# SCH_PCBBoardProject_2022-06-28.net
KiCad netlist of a schematic drawn in EasyEDA
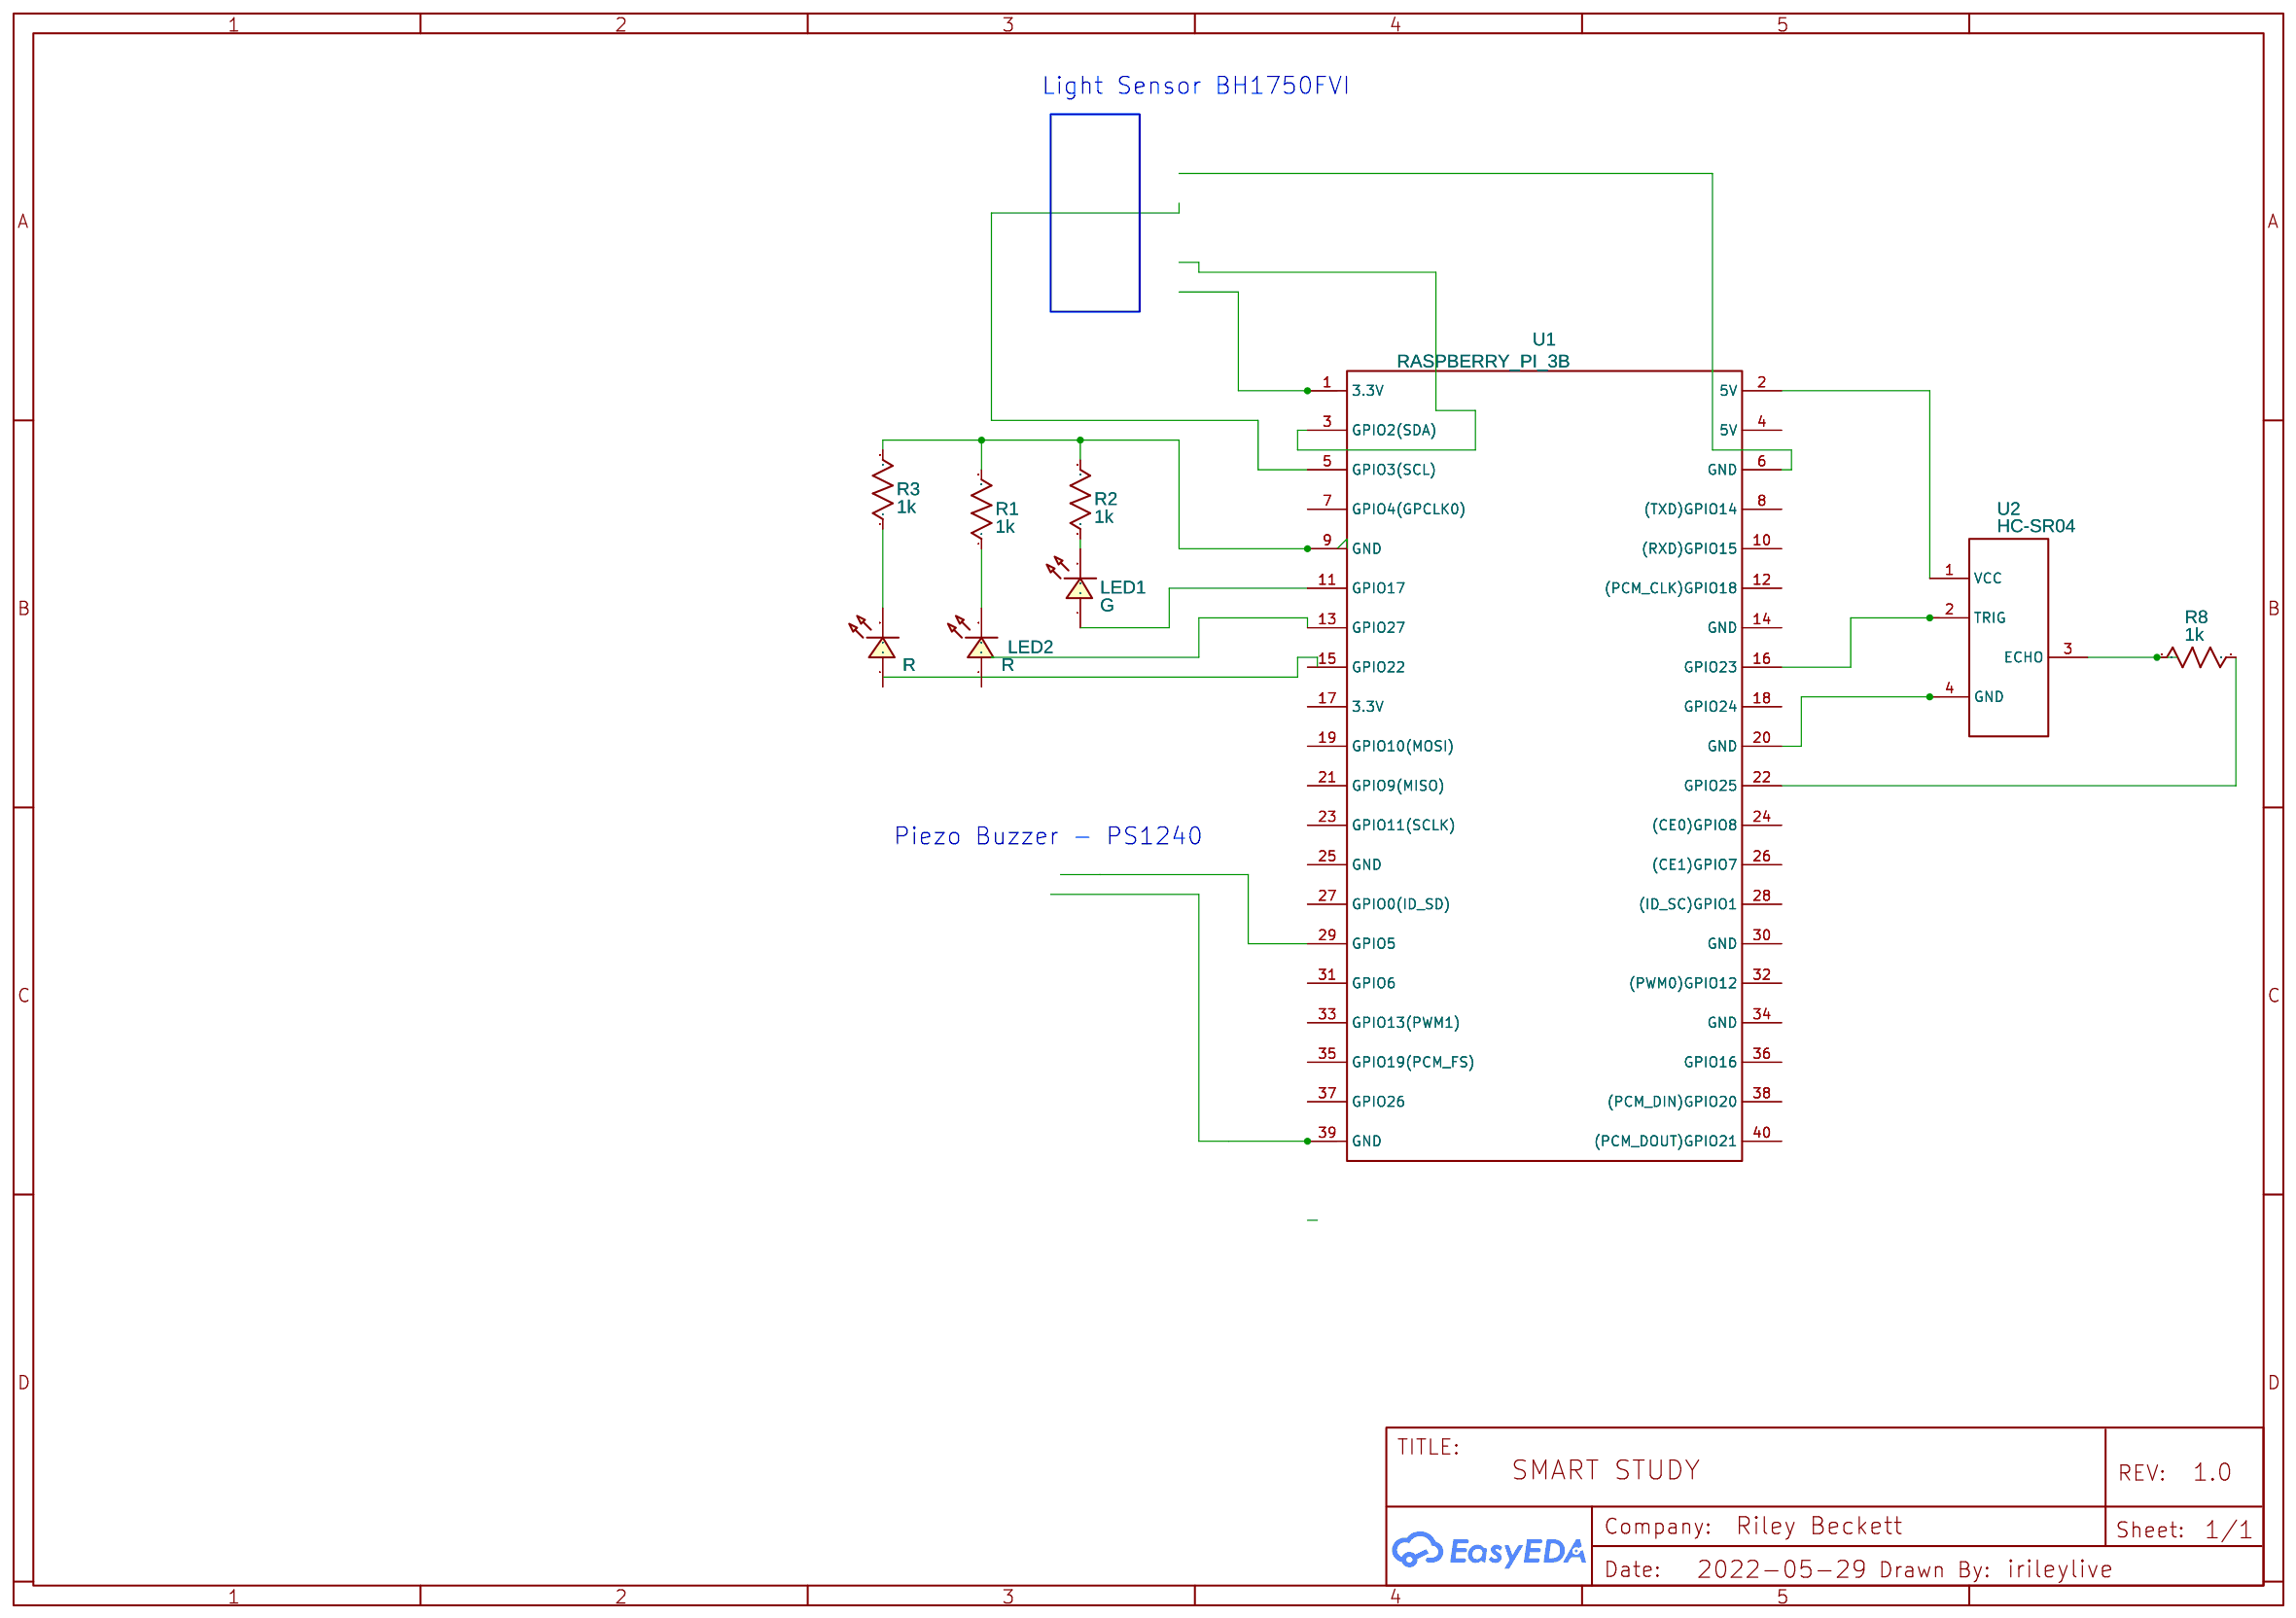
[diagram p0: schematic sheet]

(export (version "E")
  (design (tool "Eeschema 10.0.6"))
  (components
    (comp (ref "LED1")
      (value "G")
      (fields
        (field (name "BOM_Manufacturer Part") "204-10SYGD/S530-E3")
        (field (name "BOM_Supplier Part") "C85161")
      )
      (libsource (lib "") (part "LED-TH-3mm_G"))
    )
    (comp (ref "LED2")
      (value "R")
      (fields
        (field (name "BOM_Manufacturer Part") "204-10SDRD/S530-A3-L")
        (field (name "BOM_Supplier Part") "C84774")
      )
      (libsource (lib "") (part "LED-TH-3mm_R"))
    )
    (comp (ref "LED3")
      (value "R")
      (fields
        (field (name "BOM_Manufacturer Part") "204-10SDRD/S530-A3-L")
        (field (name "BOM_Supplier Part") "C84774")
      )
      (libsource (lib "") (part "LED-TH-3mm_R"))
    )
    (comp (ref "R1") (value "1k") (libsource (lib "") (part "R_AXIAL-0.3_US")))
    (comp (ref "R2") (value "1k") (libsource (lib "") (part "R_AXIAL-0.3_US")))
    (comp (ref "R3") (value "1k") (libsource (lib "") (part "R_AXIAL-0.3_US")))
    (comp (ref "R8") (value "1k") (libsource (lib "") (part "R_AXIAL-0.3_US_1")))
    (comp (ref "U1")
      (value "RASPBERRY_PI_3B")
      (fields (field (name "BOM_Manufacturer Part") "Raspberry-Pi-3B-Plus-HAT-Board"))
      (libsource (lib "") (part "RASPBERRY_PI_3B_PLUS_HAT_BOARD"))
    )
    (comp (ref "U2") (value "HC-SR04") (libsource (lib "") (part "HC-SR04")))
  )
  (nets
    (net (code "1") (name "Net-(LED1-Pad2)") (class "Default")
      (node (ref "LED1") (pin "2") (pinfunction "2_2") (pintype "unspecified"))
      (node (ref "R2") (pin "1") (pinfunction "1_1") (pintype "unspecified"))
    )
    (net (code "2") (name "Net-(LED2-Pad2)") (class "Default")
      (node (ref "LED2") (pin "2") (pinfunction "2_2") (pintype "unspecified"))
      (node (ref "R1") (pin "1") (pinfunction "1_1") (pintype "unspecified"))
    )
    (net (code "3") (name "Net-(LED3-Pad2)") (class "Default")
      (node (ref "LED3") (pin "2") (pinfunction "2_2") (pintype "unspecified"))
      (node (ref "R3") (pin "1") (pinfunction "1_1") (pintype "unspecified"))
    )
    (net (code "4") (name "Net-(R1-Pad2)") (class "Default")
      (node (ref "R1") (pin "2") (pinfunction "2_2") (pintype "unspecified"))
      (node (ref "R2") (pin "2") (pinfunction "2_2") (pintype "unspecified"))
      (node (ref "R3") (pin "2") (pinfunction "2_2") (pintype "unspecified"))
      (node (ref "U1") (pin "9") (pinfunction "GND_9") (pintype "unspecified"))
    )
    (net (code "5") (name "Net-(U1-GPIO17)") (class "Default")
      (node (ref "LED1") (pin "1") (pinfunction "1_1") (pintype "unspecified"))
      (node (ref "U1") (pin "11") (pinfunction "GPIO17_11") (pintype "unspecified"))
    )
    (net (code "6") (name "Net-(U1-GPIO23)") (class "Default")
      (node (ref "U1") (pin "16") (pinfunction "GPIO23_16") (pintype "unspecified"))
      (node (ref "U2") (pin "2") (pinfunction "TRIG_2") (pintype "unspecified"))
    )
    (net (code "7") (name "Net-(U1-GPIO25)") (class "Default")
      (node (ref "R8") (pin "1") (pinfunction "1_1") (pintype "unspecified"))
      (node (ref "U1") (pin "22") (pinfunction "GPIO25_22") (pintype "unspecified"))
    )
    (net (code "8") (name "Net-(U2-ECHO)") (class "Default")
      (node (ref "R8") (pin "2") (pinfunction "2_2") (pintype "unspecified"))
      (node (ref "U2") (pin "3") (pinfunction "ECHO_3") (pintype "unspecified"))
    )
    (net (code "9") (name "Net-(U2-GND)") (class "Default")
      (node (ref "U1") (pin "20") (pinfunction "GND_20") (pintype "unspecified"))
      (node (ref "U2") (pin "4") (pinfunction "GND_4") (pintype "unspecified"))
    )
    (net (code "10") (name "Net-(U2-VCC)") (class "Default")
      (node (ref "U1") (pin "2") (pinfunction "5V_2") (pintype "unspecified"))
      (node (ref "U2") (pin "1") (pinfunction "VCC_1") (pintype "unspecified"))
    )
    (net (code "11") (name "unconnected-(LED2-Pad1)") (class "Default")
      (node (ref "LED2") (pin "1") (pinfunction "1_1") (pintype "unspecified"))
    )
    (net (code "12") (name "unconnected-(LED3-Pad1)") (class "Default")
      (node (ref "LED3") (pin "1") (pinfunction "1_1") (pintype "unspecified"))
    )
    (net (code "13") (name "unconnected-(U1-(CE0)GPIO8-Pad24)") (class "Default")
      (node (ref "U1") (pin "24") (pinfunction "(CE0)GPIO8_24") (pintype "unspecified"))
    )
    (net (code "14") (name "unconnected-(U1-(CE1)GPIO7-Pad26)") (class "Default")
      (node (ref "U1") (pin "26") (pinfunction "(CE1)GPIO7_26") (pintype "unspecified"))
    )
    (net (code "15") (name "unconnected-(U1-(ID_SC)GPIO1-Pad28)") (class "Default")
      (node (ref "U1") (pin "28") (pinfunction "(ID_SC)GPIO1_28") (pintype "unspecified"))
    )
    (net (code "16") (name "unconnected-(U1-(PCM_CLK)GPIO18-Pad12)") (class "Default")
      (node (ref "U1") (pin "12") (pinfunction "(PCM_CLK)GPIO18_12") (pintype "unspecified"))
    )
    (net (code "17") (name "unconnected-(U1-(PCM_DIN)GPIO20-Pad38)") (class "Default")
      (node (ref "U1") (pin "38") (pinfunction "(PCM_DIN)GPIO20_38") (pintype "unspecified"))
    )
    (net (code "18") (name "unconnected-(U1-(PCM_DOUT)GPIO21-Pad40)") (class "Default")
      (node (ref "U1") (pin "40") (pinfunction "(PCM_DOUT)GPIO21_40") (pintype "unspecified"))
    )
    (net (code "19") (name "unconnected-(U1-(PWM0)GPIO12-Pad32)") (class "Default")
      (node (ref "U1") (pin "32") (pinfunction "(PWM0)GPIO12_32") (pintype "unspecified"))
    )
    (net (code "20") (name "unconnected-(U1-(RXD)GPIO15-Pad10)") (class "Default")
      (node (ref "U1") (pin "10") (pinfunction "(RXD)GPIO15_10") (pintype "unspecified"))
    )
    (net (code "21") (name "unconnected-(U1-(TXD)GPIO14-Pad8)") (class "Default")
      (node (ref "U1") (pin "8") (pinfunction "(TXD)GPIO14_8") (pintype "unspecified"))
    )
    (net (code "22") (name "unconnected-(U1-3.3V-Pad1)") (class "Default")
      (node (ref "U1") (pin "1") (pinfunction "3.3V_1") (pintype "unspecified"))
    )
    (net (code "23") (name "unconnected-(U1-3.3V-Pad17)") (class "Default")
      (node (ref "U1") (pin "17") (pinfunction "3.3V_17") (pintype "unspecified"))
    )
    (net (code "24") (name "unconnected-(U1-5V-Pad4)") (class "Default")
      (node (ref "U1") (pin "4") (pinfunction "5V_4") (pintype "unspecified"))
    )
    (net (code "25") (name "unconnected-(U1-GND-Pad6)") (class "Default")
      (node (ref "U1") (pin "6") (pinfunction "GND_6") (pintype "unspecified"))
    )
    (net (code "26") (name "unconnected-(U1-GND-Pad14)") (class "Default")
      (node (ref "U1") (pin "14") (pinfunction "GND_14") (pintype "unspecified"))
    )
    (net (code "27") (name "unconnected-(U1-GND-Pad25)") (class "Default")
      (node (ref "U1") (pin "25") (pinfunction "GND_25") (pintype "unspecified"))
    )
    (net (code "28") (name "unconnected-(U1-GND-Pad30)") (class "Default")
      (node (ref "U1") (pin "30") (pinfunction "GND_30") (pintype "unspecified"))
    )
    (net (code "29") (name "unconnected-(U1-GND-Pad34)") (class "Default")
      (node (ref "U1") (pin "34") (pinfunction "GND_34") (pintype "unspecified"))
    )
    (net (code "30") (name "unconnected-(U1-GND-Pad39)") (class "Default")
      (node (ref "U1") (pin "39") (pinfunction "GND_39") (pintype "unspecified"))
    )
    (net (code "31") (name "unconnected-(U1-GPIO0(ID_SD)-Pad27)") (class "Default")
      (node (ref "U1") (pin "27") (pinfunction "GPIO0(ID_SD)_27") (pintype "unspecified"))
    )
    (net (code "32") (name "unconnected-(U1-GPIO2(SDA)-Pad3)") (class "Default")
      (node (ref "U1") (pin "3") (pinfunction "GPIO2(SDA)_3") (pintype "unspecified"))
    )
    (net (code "33") (name "unconnected-(U1-GPIO3(SCL)-Pad5)") (class "Default")
      (node (ref "U1") (pin "5") (pinfunction "GPIO3(SCL)_5") (pintype "unspecified"))
    )
    (net (code "34") (name "unconnected-(U1-GPIO4(GPCLK0)-Pad7)") (class "Default")
      (node (ref "U1") (pin "7") (pinfunction "GPIO4(GPCLK0)_7") (pintype "unspecified"))
    )
    (net (code "35") (name "unconnected-(U1-GPIO5-Pad29)") (class "Default")
      (node (ref "U1") (pin "29") (pinfunction "GPIO5_29") (pintype "unspecified"))
    )
    (net (code "36") (name "unconnected-(U1-GPIO6-Pad31)") (class "Default")
      (node (ref "U1") (pin "31") (pinfunction "GPIO6_31") (pintype "unspecified"))
    )
    (net (code "37") (name "unconnected-(U1-GPIO9(MISO)-Pad21)") (class "Default")
      (node (ref "U1") (pin "21") (pinfunction "GPIO9(MISO)_21") (pintype "unspecified"))
    )
    (net (code "38") (name "unconnected-(U1-GPIO10(MOSI)-Pad19)") (class "Default")
      (node (ref "U1") (pin "19") (pinfunction "GPIO10(MOSI)_19") (pintype "unspecified"))
    )
    (net (code "39") (name "unconnected-(U1-GPIO11(SCLK)-Pad23)") (class "Default")
      (node (ref "U1") (pin "23") (pinfunction "GPIO11(SCLK)_23") (pintype "unspecified"))
    )
    (net (code "40") (name "unconnected-(U1-GPIO13(PWM1)-Pad33)") (class "Default")
      (node (ref "U1") (pin "33") (pinfunction "GPIO13(PWM1)_33") (pintype "unspecified"))
    )
    (net (code "41") (name "unconnected-(U1-GPIO16-Pad36)") (class "Default")
      (node (ref "U1") (pin "36") (pinfunction "GPIO16_36") (pintype "unspecified"))
    )
    (net (code "42") (name "unconnected-(U1-GPIO19(PCM_FS)-Pad35)") (class "Default")
      (node (ref "U1") (pin "35") (pinfunction "GPIO19(PCM_FS)_35") (pintype "unspecified"))
    )
    (net (code "43") (name "unconnected-(U1-GPIO22-Pad15)") (class "Default")
      (node (ref "U1") (pin "15") (pinfunction "GPIO22_15") (pintype "unspecified"))
    )
    (net (code "44") (name "unconnected-(U1-GPIO24-Pad18)") (class "Default")
      (node (ref "U1") (pin "18") (pinfunction "GPIO24_18") (pintype "unspecified"))
    )
    (net (code "45") (name "unconnected-(U1-GPIO26-Pad37)") (class "Default")
      (node (ref "U1") (pin "37") (pinfunction "GPIO26_37") (pintype "unspecified"))
    )
    (net (code "46") (name "unconnected-(U1-GPIO27-Pad13)") (class "Default")
      (node (ref "U1") (pin "13") (pinfunction "GPIO27_13") (pintype "unspecified"))
    )
  )
)
